# SHOW.net
KiCad netlist of a schematic drawn in Altium Designer
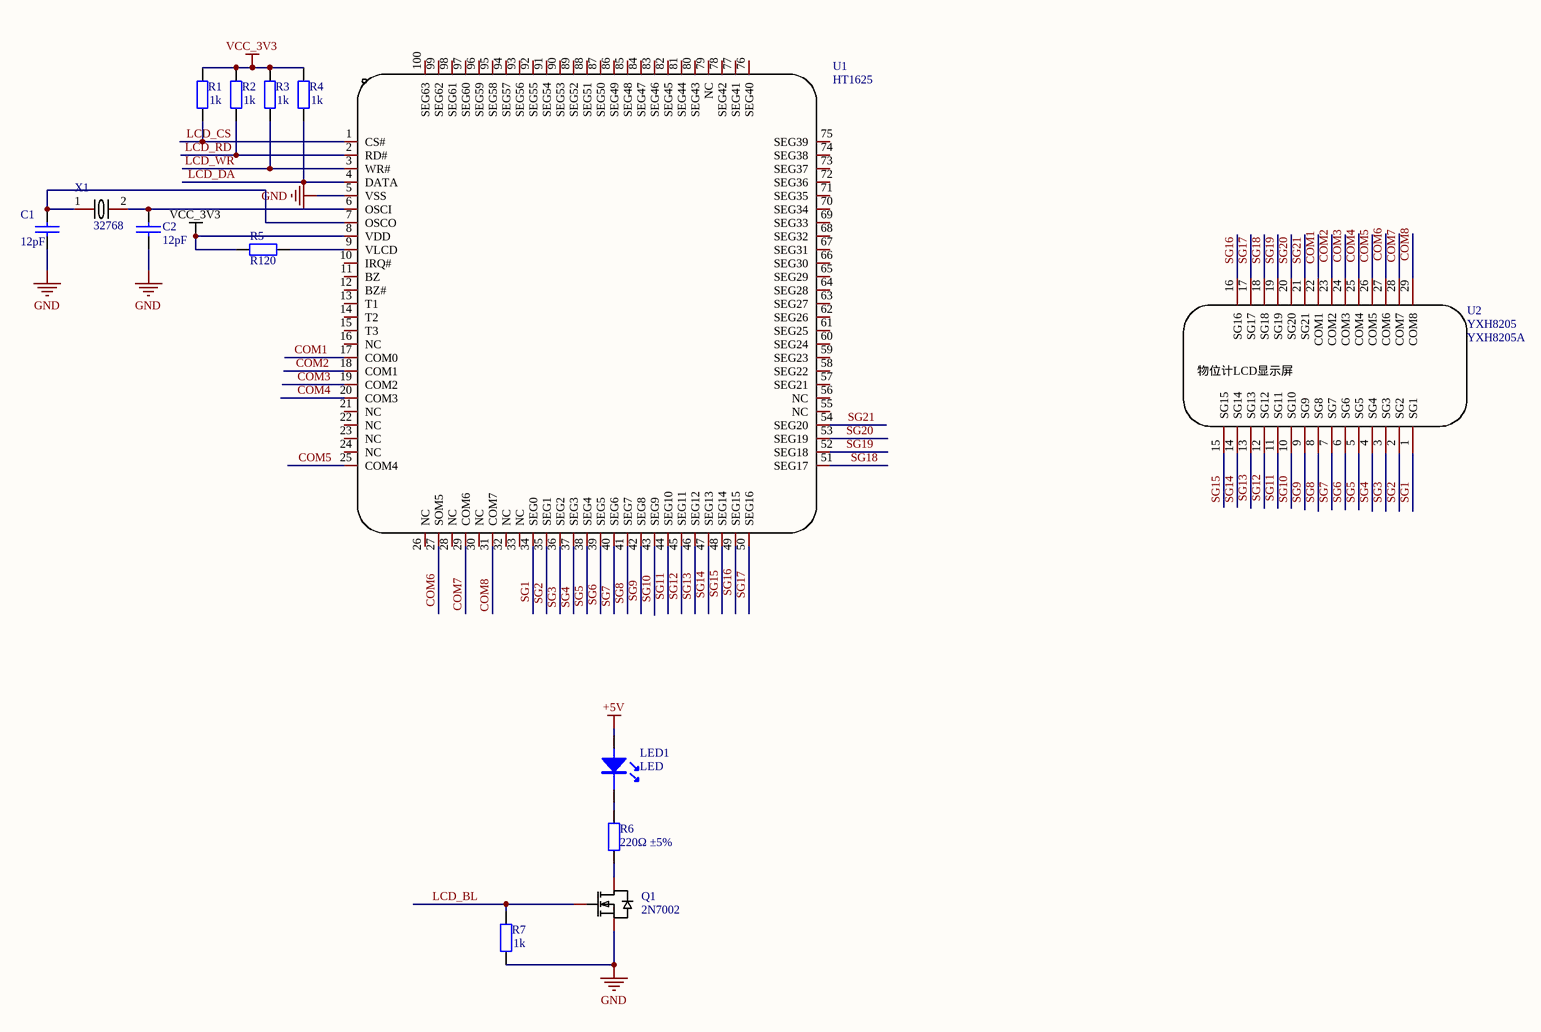
[diagram p0: SHOW.SchDoc]

(export (version "E")
  (design (tool "Eeschema 10.0.6"))
  (components
    (comp (ref "C1")
      (value "12pF")
      (footprint "C-0805")
      (description "电容")
      (libsource (lib "泰开常用器件") (part "C普通电容"))
    )
    (comp (ref "C2")
      (value "12pF")
      (footprint "C-0805")
      (description "电容")
      (libsource (lib "泰开常用器件") (part "C普通电容"))
    )
    (comp (ref "LED1") (value "LED") (footprint "LED0805-R-RD") (libsource (lib "泰开常用器件(3)") (part "LED")))
    (comp (ref "Q1")
      (value "2N7002")
      (footprint "SOT-23-3")
      (fields (field (name "NAME") "2N7002") (field (name "MANUFACTURER") "CJ（江苏长电/长晶）"))
      (libsource (lib "altium-import") (part "root_0_2N7002_C8545_"))
    )
    (comp (ref "R1")
      (value "1k")
      (footprint "R-0805")
      (description "电阻")
      (fields (field (name "PUBLISHER") "Altium Limited"))
      (libsource (lib "泰开常用器件") (part "RES"))
    )
    (comp (ref "R2")
      (value "1k")
      (footprint "R-0805")
      (description "电阻")
      (fields (field (name "PUBLISHER") "Altium Limited"))
      (libsource (lib "泰开常用器件") (part "RES"))
    )
    (comp (ref "R3")
      (value "1k")
      (footprint "R-0805")
      (description "电阻")
      (fields (field (name "PUBLISHER") "Altium Limited"))
      (libsource (lib "泰开常用器件") (part "RES"))
    )
    (comp (ref "R4")
      (value "1k")
      (footprint "R-0805")
      (description "电阻")
      (fields (field (name "PUBLISHER") "Altium Limited"))
      (libsource (lib "泰开常用器件") (part "RES"))
    )
    (comp (ref "R5")
      (value "R120")
      (footprint "R-0805")
      (description "电阻")
      (fields (field (name "PUBLISHER") "Altium Limited"))
      (libsource (lib "") (part "RES_1"))
    )
    (comp (ref "R6")
      (value "220Ω ±5%")
      (footprint "R-0805")
      (description "电阻")
      (fields (field (name "PUBLISHER") "Altium Limited"))
      (libsource (lib "泰开常用器件(3)") (part "RES"))
    )
    (comp (ref "R7")
      (value "1k")
      (footprint "R-0805")
      (description "电阻")
      (fields (field (name "PUBLISHER") "Altium Limited"))
      (libsource (lib "泰开常用器件") (part "RES"))
    )
    (comp (ref "U1")
      (value "HT1625")
      (footprint "LQFP-100_L14.0-W14.0-P0.50-LS16.0-BL - duplicate")
      (libsource (lib "泰开常用器件") (part "HT1625"))
    )
    (comp (ref "U2")
      (value "YXH8205")
      (footprint "YXH8205A")
      (fields (field (name "NAME") "YXH8205") (field (name "DEVICE") "YXH8205A"))
      (libsource (lib "altium-import") (part "root_0_YXH8205A_"))
    )
    (comp (ref "X1")
      (value "32768")
      (footprint "CRYSTAL-SMD_L3.2-W1.5")
      (libsource (lib "泰开常用器件") (part "7N032768NW2"))
    )
  )
  (nets
    (net (code "1") (name "+5V") (class "Default")
      (node (ref "LED1") (pin "1") (pinfunction "1_1") (pintype "passive"))
    )
    (net (code "2") (name "/COM1") (class "Default")
      (node (ref "U1") (pin "17") (pinfunction "COM0_17") (pintype "passive"))
      (node (ref "U2") (pin "22") (pinfunction "COM1_22") (pintype "passive"))
    )
    (net (code "3") (name "/COM2") (class "Default")
      (node (ref "U1") (pin "18") (pinfunction "COM1_18") (pintype "passive"))
      (node (ref "U2") (pin "23") (pinfunction "COM2_23") (pintype "passive"))
    )
    (net (code "4") (name "/COM3") (class "Default")
      (node (ref "U1") (pin "19") (pinfunction "COM2_19") (pintype "passive"))
      (node (ref "U2") (pin "24") (pinfunction "COM3_24") (pintype "passive"))
    )
    (net (code "5") (name "/COM4") (class "Default")
      (node (ref "U1") (pin "20") (pinfunction "COM3_20") (pintype "passive"))
      (node (ref "U2") (pin "25") (pinfunction "COM4_25") (pintype "passive"))
    )
    (net (code "6") (name "/COM5") (class "Default")
      (node (ref "U1") (pin "25") (pinfunction "COM4_25") (pintype "passive"))
      (node (ref "U2") (pin "26") (pinfunction "COM5_26") (pintype "passive"))
    )
    (net (code "7") (name "/COM6") (class "Default")
      (node (ref "U1") (pin "27") (pinfunction "SOM5_27") (pintype "passive"))
      (node (ref "U2") (pin "27") (pinfunction "COM6_27") (pintype "passive"))
    )
    (net (code "8") (name "/COM7") (class "Default")
      (node (ref "U1") (pin "29") (pinfunction "COM6_29") (pintype "passive"))
      (node (ref "U2") (pin "28") (pinfunction "COM7_28") (pintype "passive"))
    )
    (net (code "9") (name "/COM8") (class "Default")
      (node (ref "U1") (pin "31") (pinfunction "COM7_31") (pintype "passive"))
      (node (ref "U2") (pin "29") (pinfunction "COM8_29") (pintype "passive"))
    )
    (net (code "10") (name "/LCD_BL") (class "Default")
      (node (ref "Q1") (pin "1") (pinfunction "G_1") (pintype "passive"))
      (node (ref "R7") (pin "2") (pinfunction "2_2") (pintype "passive"))
    )
    (net (code "11") (name "/LCD_CS") (class "Default")
      (node (ref "R1") (pin "1") (pinfunction "1_1") (pintype "passive"))
      (node (ref "U1") (pin "1") (pinfunction "CS#_1") (pintype "passive"))
    )
    (net (code "12") (name "/LCD_DA") (class "Default")
      (node (ref "R4") (pin "1") (pinfunction "1_1") (pintype "passive"))
      (node (ref "U1") (pin "4") (pinfunction "DATA_4") (pintype "passive"))
    )
    (net (code "13") (name "/LCD_RD") (class "Default")
      (node (ref "R2") (pin "1") (pinfunction "1_1") (pintype "passive"))
      (node (ref "U1") (pin "2") (pinfunction "RD#_2") (pintype "passive"))
    )
    (net (code "14") (name "/LCD_WR") (class "Default")
      (node (ref "R3") (pin "1") (pinfunction "1_1") (pintype "passive"))
      (node (ref "U1") (pin "3") (pinfunction "WR#_3") (pintype "passive"))
    )
    (net (code "15") (name "/SG1") (class "Default")
      (node (ref "U1") (pin "34") (pinfunction "SEG0_34") (pintype "passive"))
      (node (ref "U2") (pin "1") (pinfunction "SG1_1") (pintype "passive"))
    )
    (net (code "16") (name "/SG2") (class "Default")
      (node (ref "U1") (pin "35") (pinfunction "SEG1_35") (pintype "passive"))
      (node (ref "U2") (pin "2") (pinfunction "SG2_2") (pintype "passive"))
    )
    (net (code "17") (name "/SG3") (class "Default")
      (node (ref "U1") (pin "36") (pinfunction "SEG2_36") (pintype "passive"))
      (node (ref "U2") (pin "3") (pinfunction "SG3_3") (pintype "passive"))
    )
    (net (code "18") (name "/SG4") (class "Default")
      (node (ref "U1") (pin "37") (pinfunction "SEG3_37") (pintype "passive"))
      (node (ref "U2") (pin "4") (pinfunction "SG4_4") (pintype "passive"))
    )
    (net (code "19") (name "/SG5") (class "Default")
      (node (ref "U1") (pin "38") (pinfunction "SEG4_38") (pintype "passive"))
      (node (ref "U2") (pin "5") (pinfunction "SG5_5") (pintype "passive"))
    )
    (net (code "20") (name "/SG6") (class "Default")
      (node (ref "U1") (pin "39") (pinfunction "SEG5_39") (pintype "passive"))
      (node (ref "U2") (pin "6") (pinfunction "SG6_6") (pintype "passive"))
    )
    (net (code "21") (name "/SG7") (class "Default")
      (node (ref "U1") (pin "40") (pinfunction "SEG6_40") (pintype "passive"))
      (node (ref "U2") (pin "7") (pinfunction "SG7_7") (pintype "passive"))
    )
    (net (code "22") (name "/SG8") (class "Default")
      (node (ref "U1") (pin "41") (pinfunction "SEG7_41") (pintype "passive"))
      (node (ref "U2") (pin "8") (pinfunction "SG8_8") (pintype "passive"))
    )
    (net (code "23") (name "/SG9") (class "Default")
      (node (ref "U1") (pin "42") (pinfunction "SEG8_42") (pintype "passive"))
      (node (ref "U2") (pin "9") (pinfunction "SG9_9") (pintype "passive"))
    )
    (net (code "24") (name "/SG10") (class "Default")
      (node (ref "U1") (pin "43") (pinfunction "SEG9_43") (pintype "passive"))
      (node (ref "U2") (pin "10") (pinfunction "SG10_10") (pintype "passive"))
    )
    (net (code "25") (name "/SG11") (class "Default")
      (node (ref "U1") (pin "44") (pinfunction "SEG10_44") (pintype "passive"))
      (node (ref "U2") (pin "11") (pinfunction "SG11_11") (pintype "passive"))
    )
    (net (code "26") (name "/SG12") (class "Default")
      (node (ref "U1") (pin "45") (pinfunction "SEG11_45") (pintype "passive"))
      (node (ref "U2") (pin "12") (pinfunction "SG12_12") (pintype "passive"))
    )
    (net (code "27") (name "/SG13") (class "Default")
      (node (ref "U1") (pin "46") (pinfunction "SEG12_46") (pintype "passive"))
      (node (ref "U2") (pin "13") (pinfunction "SG13_13") (pintype "passive"))
    )
    (net (code "28") (name "/SG14") (class "Default")
      (node (ref "U1") (pin "47") (pinfunction "SEG13_47") (pintype "passive"))
      (node (ref "U2") (pin "14") (pinfunction "SG14_14") (pintype "passive"))
    )
    (net (code "29") (name "/SG15") (class "Default")
      (node (ref "U1") (pin "48") (pinfunction "SEG14_48") (pintype "passive"))
      (node (ref "U2") (pin "15") (pinfunction "SG15_15") (pintype "passive"))
    )
    (net (code "30") (name "/SG16") (class "Default")
      (node (ref "U1") (pin "49") (pinfunction "SEG15_49") (pintype "passive"))
      (node (ref "U2") (pin "16") (pinfunction "SG16_16") (pintype "passive"))
    )
    (net (code "31") (name "/SG17") (class "Default")
      (node (ref "U1") (pin "50") (pinfunction "SEG16_50") (pintype "passive"))
      (node (ref "U2") (pin "17") (pinfunction "SG17_17") (pintype "passive"))
    )
    (net (code "32") (name "/SG18") (class "Default")
      (node (ref "U1") (pin "51") (pinfunction "SEG17_51") (pintype "passive"))
      (node (ref "U2") (pin "18") (pinfunction "SG18_18") (pintype "passive"))
    )
    (net (code "33") (name "/SG19") (class "Default")
      (node (ref "U1") (pin "52") (pinfunction "SEG18_52") (pintype "passive"))
      (node (ref "U2") (pin "19") (pinfunction "SG19_19") (pintype "passive"))
    )
    (net (code "34") (name "/SG20") (class "Default")
      (node (ref "U1") (pin "53") (pinfunction "SEG19_53") (pintype "passive"))
      (node (ref "U2") (pin "20") (pinfunction "SG20_20") (pintype "passive"))
    )
    (net (code "35") (name "/SG21") (class "Default")
      (node (ref "U1") (pin "54") (pinfunction "SEG20_54") (pintype "passive"))
      (node (ref "U2") (pin "21") (pinfunction "SG21_21") (pintype "passive"))
    )
    (net (code "36") (name "GND") (class "Default")
      (node (ref "C1") (pin "1") (pinfunction "1_1") (pintype "passive"))
      (node (ref "C2") (pin "1") (pinfunction "1_1") (pintype "passive"))
      (node (ref "Q1") (pin "2") (pinfunction "S_2") (pintype "passive"))
      (node (ref "R7") (pin "1") (pinfunction "1_1") (pintype "passive"))
      (node (ref "U1") (pin "5") (pinfunction "VSS_5") (pintype "passive"))
    )
    (net (code "37") (name "Net-(LED1-Pad2)") (class "Default")
      (node (ref "LED1") (pin "2") (pinfunction "2_2") (pintype "passive"))
      (node (ref "R6") (pin "2") (pinfunction "2_2") (pintype "passive"))
    )
    (net (code "38") (name "Net-(Q1-D)") (class "Default")
      (node (ref "Q1") (pin "3") (pinfunction "D_3") (pintype "passive"))
      (node (ref "R6") (pin "1") (pinfunction "1_1") (pintype "passive"))
    )
    (net (code "39") (name "Net-(U1-OSCI)") (class "Default")
      (node (ref "C2") (pin "2") (pinfunction "2_2") (pintype "passive"))
      (node (ref "U1") (pin "6") (pinfunction "OSCI_6") (pintype "passive"))
      (node (ref "X1") (pin "2") (pinfunction "2_2") (pintype "passive"))
    )
    (net (code "40") (name "Net-(U1-OSCO)") (class "Default")
      (node (ref "C1") (pin "2") (pinfunction "2_2") (pintype "passive"))
      (node (ref "U1") (pin "7") (pinfunction "OSCO_7") (pintype "passive"))
      (node (ref "X1") (pin "1") (pinfunction "1_1") (pintype "passive"))
    )
    (net (code "41") (name "Net-(U1-VLCD)") (class "Default")
      (node (ref "R5") (pin "1") (pinfunction "1_1") (pintype "passive"))
      (node (ref "U1") (pin "9") (pinfunction "VLCD_9") (pintype "passive"))
    )
    (net (code "42") (name "VCC_3V3") (class "Default")
      (node (ref "R1") (pin "2") (pinfunction "2_2") (pintype "passive"))
      (node (ref "R2") (pin "2") (pinfunction "2_2") (pintype "passive"))
      (node (ref "R3") (pin "2") (pinfunction "2_2") (pintype "passive"))
      (node (ref "R4") (pin "2") (pinfunction "2_2") (pintype "passive"))
      (node (ref "R5") (pin "2") (pinfunction "2_2") (pintype "passive"))
      (node (ref "U1") (pin "8") (pinfunction "VDD_8") (pintype "passive"))
    )
    (net (code "43") (name "unconnected-(U1-BZ#-Pad12)") (class "Default")
      (node (ref "U1") (pin "12") (pinfunction "BZ#_12") (pintype "passive"))
    )
    (net (code "44") (name "unconnected-(U1-BZ-Pad11)") (class "Default")
      (node (ref "U1") (pin "11") (pinfunction "BZ_11") (pintype "passive"))
    )
    (net (code "45") (name "unconnected-(U1-IRQ#-Pad10)") (class "Default")
      (node (ref "U1") (pin "10") (pinfunction "IRQ#_10") (pintype "passive"))
    )
    (net (code "46") (name "unconnected-(U1-NC-Pad16)") (class "Default")
      (node (ref "U1") (pin "16") (pinfunction "NC_16") (pintype "passive"))
    )
    (net (code "47") (name "unconnected-(U1-NC-Pad21)") (class "Default")
      (node (ref "U1") (pin "21") (pinfunction "NC_21") (pintype "passive"))
    )
    (net (code "48") (name "unconnected-(U1-NC-Pad22)") (class "Default")
      (node (ref "U1") (pin "22") (pinfunction "NC_22") (pintype "passive"))
    )
    (net (code "49") (name "unconnected-(U1-NC-Pad23)") (class "Default")
      (node (ref "U1") (pin "23") (pinfunction "NC_23") (pintype "passive"))
    )
    (net (code "50") (name "unconnected-(U1-NC-Pad24)") (class "Default")
      (node (ref "U1") (pin "24") (pinfunction "NC_24") (pintype "passive"))
    )
    (net (code "51") (name "unconnected-(U1-NC-Pad26)") (class "Default")
      (node (ref "U1") (pin "26") (pinfunction "NC_26") (pintype "passive"))
    )
    (net (code "52") (name "unconnected-(U1-NC-Pad28)") (class "Default")
      (node (ref "U1") (pin "28") (pinfunction "NC_28") (pintype "passive"))
    )
    (net (code "53") (name "unconnected-(U1-NC-Pad30)") (class "Default")
      (node (ref "U1") (pin "30") (pinfunction "NC_30") (pintype "passive"))
    )
    (net (code "54") (name "unconnected-(U1-NC-Pad32)") (class "Default")
      (node (ref "U1") (pin "32") (pinfunction "NC_32") (pintype "passive"))
    )
    (net (code "55") (name "unconnected-(U1-NC-Pad33)") (class "Default")
      (node (ref "U1") (pin "33") (pinfunction "NC_33") (pintype "passive"))
    )
    (net (code "56") (name "unconnected-(U1-NC-Pad55)") (class "Default")
      (node (ref "U1") (pin "55") (pinfunction "NC_55") (pintype "passive"))
    )
    (net (code "57") (name "unconnected-(U1-NC-Pad56)") (class "Default")
      (node (ref "U1") (pin "56") (pinfunction "NC_56") (pintype "passive"))
    )
    (net (code "58") (name "unconnected-(U1-NC-Pad79)") (class "Default")
      (node (ref "U1") (pin "79") (pinfunction "NC_79") (pintype "passive"))
    )
    (net (code "59") (name "unconnected-(U1-SEG21-Pad57)") (class "Default")
      (node (ref "U1") (pin "57") (pinfunction "SEG21_57") (pintype "passive"))
    )
    (net (code "60") (name "unconnected-(U1-SEG22-Pad58)") (class "Default")
      (node (ref "U1") (pin "58") (pinfunction "SEG22_58") (pintype "passive"))
    )
    (net (code "61") (name "unconnected-(U1-SEG23-Pad59)") (class "Default")
      (node (ref "U1") (pin "59") (pinfunction "SEG23_59") (pintype "passive"))
    )
    (net (code "62") (name "unconnected-(U1-SEG24-Pad60)") (class "Default")
      (node (ref "U1") (pin "60") (pinfunction "SEG24_60") (pintype "passive"))
    )
    (net (code "63") (name "unconnected-(U1-SEG25-Pad61)") (class "Default")
      (node (ref "U1") (pin "61") (pinfunction "SEG25_61") (pintype "passive"))
    )
    (net (code "64") (name "unconnected-(U1-SEG26-Pad62)") (class "Default")
      (node (ref "U1") (pin "62") (pinfunction "SEG26_62") (pintype "passive"))
    )
    (net (code "65") (name "unconnected-(U1-SEG27-Pad63)") (class "Default")
      (node (ref "U1") (pin "63") (pinfunction "SEG27_63") (pintype "passive"))
    )
    (net (code "66") (name "unconnected-(U1-SEG28-Pad64)") (class "Default")
      (node (ref "U1") (pin "64") (pinfunction "SEG28_64") (pintype "passive"))
    )
    (net (code "67") (name "unconnected-(U1-SEG29-Pad65)") (class "Default")
      (node (ref "U1") (pin "65") (pinfunction "SEG29_65") (pintype "passive"))
    )
    (net (code "68") (name "unconnected-(U1-SEG30-Pad66)") (class "Default")
      (node (ref "U1") (pin "66") (pinfunction "SEG30_66") (pintype "passive"))
    )
    (net (code "69") (name "unconnected-(U1-SEG31-Pad67)") (class "Default")
      (node (ref "U1") (pin "67") (pinfunction "SEG31_67") (pintype "passive"))
    )
    (net (code "70") (name "unconnected-(U1-SEG32-Pad68)") (class "Default")
      (node (ref "U1") (pin "68") (pinfunction "SEG32_68") (pintype "passive"))
    )
    (net (code "71") (name "unconnected-(U1-SEG33-Pad69)") (class "Default")
      (node (ref "U1") (pin "69") (pinfunction "SEG33_69") (pintype "passive"))
    )
    (net (code "72") (name "unconnected-(U1-SEG34-Pad70)") (class "Default")
      (node (ref "U1") (pin "70") (pinfunction "SEG34_70") (pintype "passive"))
    )
    (net (code "73") (name "unconnected-(U1-SEG35-Pad71)") (class "Default")
      (node (ref "U1") (pin "71") (pinfunction "SEG35_71") (pintype "passive"))
    )
    (net (code "74") (name "unconnected-(U1-SEG36-Pad72)") (class "Default")
      (node (ref "U1") (pin "72") (pinfunction "SEG36_72") (pintype "passive"))
    )
    (net (code "75") (name "unconnected-(U1-SEG37-Pad73)") (class "Default")
      (node (ref "U1") (pin "73") (pinfunction "SEG37_73") (pintype "passive"))
    )
    (net (code "76") (name "unconnected-(U1-SEG38-Pad74)") (class "Default")
      (node (ref "U1") (pin "74") (pinfunction "SEG38_74") (pintype "passive"))
    )
    (net (code "77") (name "unconnected-(U1-SEG39-Pad75)") (class "Default")
      (node (ref "U1") (pin "75") (pinfunction "SEG39_75") (pintype "passive"))
    )
    (net (code "78") (name "unconnected-(U1-SEG40-Pad76)") (class "Default")
      (node (ref "U1") (pin "76") (pinfunction "SEG40_76") (pintype "passive"))
    )
    (net (code "79") (name "unconnected-(U1-SEG41-Pad77)") (class "Default")
      (node (ref "U1") (pin "77") (pinfunction "SEG41_77") (pintype "passive"))
    )
    (net (code "80") (name "unconnected-(U1-SEG42-Pad78)") (class "Default")
      (node (ref "U1") (pin "78") (pinfunction "SEG42_78") (pintype "passive"))
    )
    (net (code "81") (name "unconnected-(U1-SEG43-Pad80)") (class "Default")
      (node (ref "U1") (pin "80") (pinfunction "SEG43_80") (pintype "passive"))
    )
    (net (code "82") (name "unconnected-(U1-SEG44-Pad81)") (class "Default")
      (node (ref "U1") (pin "81") (pinfunction "SEG44_81") (pintype "passive"))
    )
    (net (code "83") (name "unconnected-(U1-SEG45-Pad82)") (class "Default")
      (node (ref "U1") (pin "82") (pinfunction "SEG45_82") (pintype "passive"))
    )
    (net (code "84") (name "unconnected-(U1-SEG46-Pad83)") (class "Default")
      (node (ref "U1") (pin "83") (pinfunction "SEG46_83") (pintype "passive"))
    )
    (net (code "85") (name "unconnected-(U1-SEG47-Pad84)") (class "Default")
      (node (ref "U1") (pin "84") (pinfunction "SEG47_84") (pintype "passive"))
    )
    (net (code "86") (name "unconnected-(U1-SEG48-Pad85)") (class "Default")
      (node (ref "U1") (pin "85") (pinfunction "SEG48_85") (pintype "passive"))
    )
    (net (code "87") (name "unconnected-(U1-SEG49-Pad86)") (class "Default")
      (node (ref "U1") (pin "86") (pinfunction "SEG49_86") (pintype "passive"))
    )
    (net (code "88") (name "unconnected-(U1-SEG50-Pad87)") (class "Default")
      (node (ref "U1") (pin "87") (pinfunction "SEG50_87") (pintype "passive"))
    )
    (net (code "89") (name "unconnected-(U1-SEG51-Pad88)") (class "Default")
      (node (ref "U1") (pin "88") (pinfunction "SEG51_88") (pintype "passive"))
    )
    (net (code "90") (name "unconnected-(U1-SEG52-Pad89)") (class "Default")
      (node (ref "U1") (pin "89") (pinfunction "SEG52_89") (pintype "passive"))
    )
    (net (code "91") (name "unconnected-(U1-SEG53-Pad90)") (class "Default")
      (node (ref "U1") (pin "90") (pinfunction "SEG53_90") (pintype "passive"))
    )
    (net (code "92") (name "unconnected-(U1-SEG54-Pad91)") (class "Default")
      (node (ref "U1") (pin "91") (pinfunction "SEG54_91") (pintype "passive"))
    )
    (net (code "93") (name "unconnected-(U1-SEG55-Pad92)") (class "Default")
      (node (ref "U1") (pin "92") (pinfunction "SEG55_92") (pintype "passive"))
    )
    (net (code "94") (name "unconnected-(U1-SEG56-Pad93)") (class "Default")
      (node (ref "U1") (pin "93") (pinfunction "SEG56_93") (pintype "passive"))
    )
    (net (code "95") (name "unconnected-(U1-SEG57-Pad94)") (class "Default")
      (node (ref "U1") (pin "94") (pinfunction "SEG57_94") (pintype "passive"))
    )
    (net (code "96") (name "unconnected-(U1-SEG58-Pad95)") (class "Default")
      (node (ref "U1") (pin "95") (pinfunction "SEG58_95") (pintype "passive"))
    )
    (net (code "97") (name "unconnected-(U1-SEG59-Pad96)") (class "Default")
      (node (ref "U1") (pin "96") (pinfunction "SEG59_96") (pintype "passive"))
    )
    (net (code "98") (name "unconnected-(U1-SEG60-Pad97)") (class "Default")
      (node (ref "U1") (pin "97") (pinfunction "SEG60_97") (pintype "passive"))
    )
    (net (code "99") (name "unconnected-(U1-SEG61-Pad98)") (class "Default")
      (node (ref "U1") (pin "98") (pinfunction "SEG61_98") (pintype "passive"))
    )
    (net (code "100") (name "unconnected-(U1-SEG62-Pad99)") (class "Default")
      (node (ref "U1") (pin "99") (pinfunction "SEG62_99") (pintype "passive"))
    )
    (net (code "101") (name "unconnected-(U1-SEG63-Pad100)") (class "Default")
      (node (ref "U1") (pin "100") (pinfunction "SEG63_100") (pintype "passive"))
    )
    (net (code "102") (name "unconnected-(U1-T1-Pad13)") (class "Default")
      (node (ref "U1") (pin "13") (pinfunction "T1_13") (pintype "passive"))
    )
    (net (code "103") (name "unconnected-(U1-T2-Pad14)") (class "Default")
      (node (ref "U1") (pin "14") (pinfunction "T2_14") (pintype "passive"))
    )
    (net (code "104") (name "unconnected-(U1-T3-Pad15)") (class "Default")
      (node (ref "U1") (pin "15") (pinfunction "T3_15") (pintype "passive"))
    )
  )
)
